# Conn_PWR.net
KiCad netlist of a schematic drawn in Altium Designer
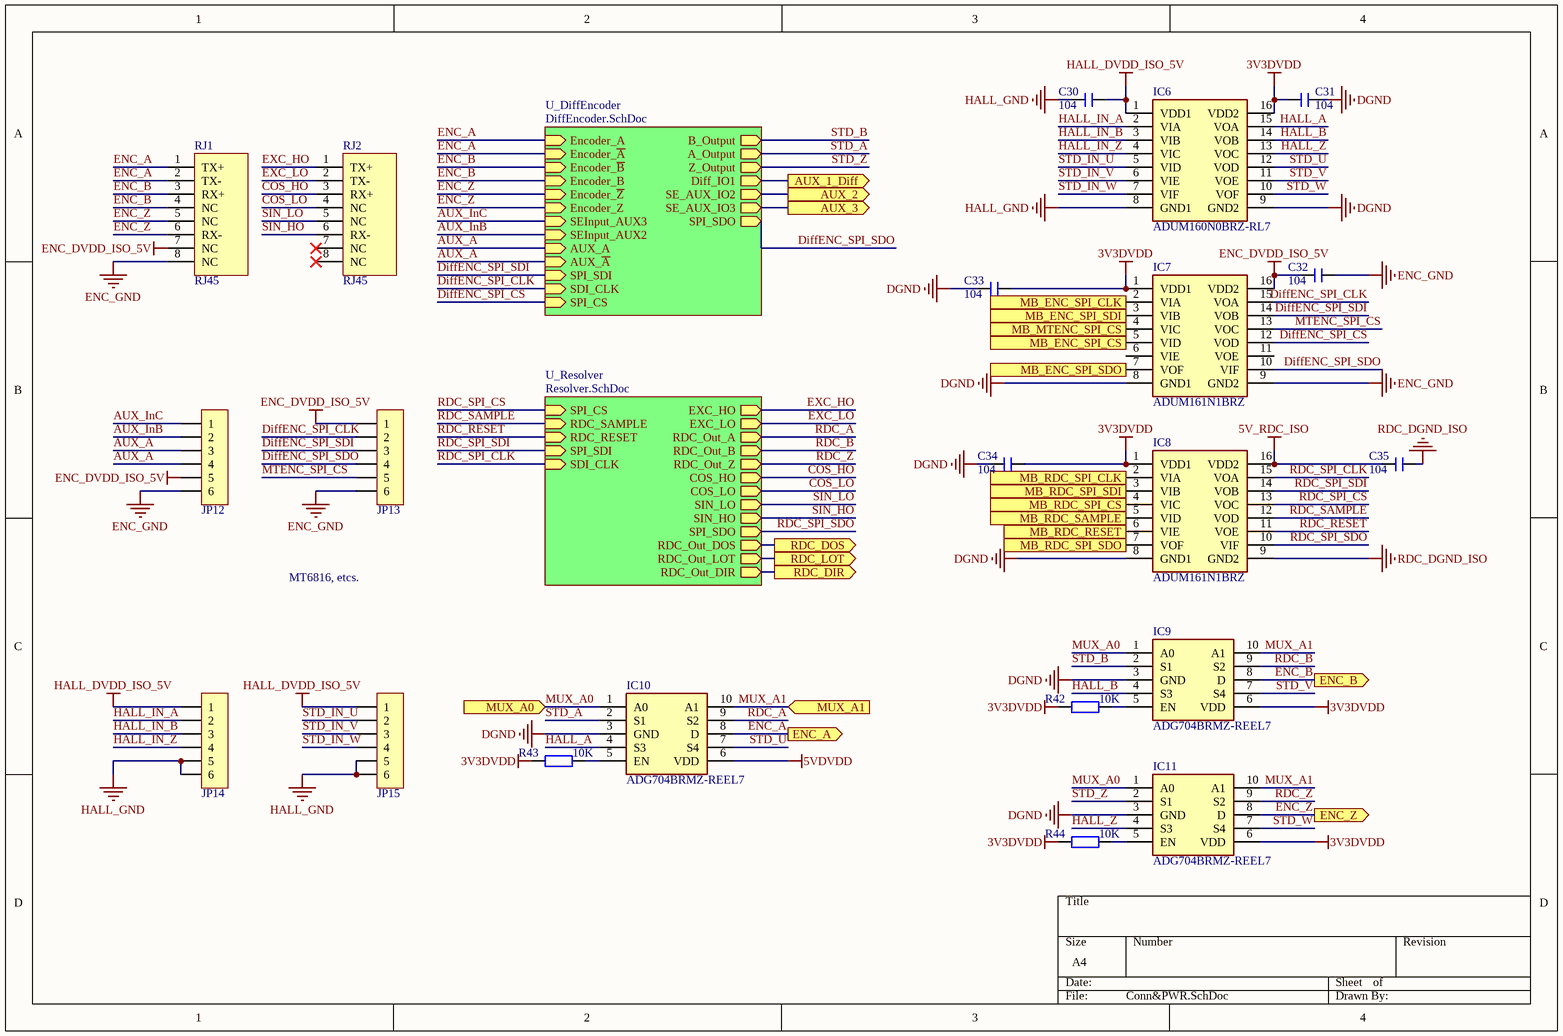
[diagram p0: Conn&PWR.SchDoc]

(export (version "E")
  (design (tool "Eeschema 10.0.6"))
  (components
    (comp (ref "C30")
      (value "104")
      (footprint "C 0603_L")
      (description "贴片电容")
      (libsource (lib "0.1 - 电阻-电容-电感") (part "C"))
    )
    (comp (ref "C31")
      (value "104")
      (footprint "C 0603_L")
      (description "贴片电容")
      (libsource (lib "0.1 - 电阻-电容-电感") (part "C"))
    )
    (comp (ref "C32")
      (value "104")
      (footprint "C 0603_L")
      (description "贴片电容")
      (libsource (lib "0.1 - 电阻-电容-电感") (part "C"))
    )
    (comp (ref "C33")
      (value "104")
      (footprint "C 0603_L")
      (description "贴片电容")
      (libsource (lib "0.1 - 电阻-电容-电感") (part "C"))
    )
    (comp (ref "C34")
      (value "104")
      (footprint "C 0603_L")
      (description "贴片电容")
      (libsource (lib "0.1 - 电阻-电容-电感") (part "C"))
    )
    (comp (ref "C35")
      (value "104")
      (footprint "C 0603_L")
      (description "贴片电容")
      (libsource (lib "0.1 - 电阻-电容-电感") (part "C"))
    )
    (comp (ref "IC6")
      (value "ADUM160N0BRZ-RL7")
      (footprint "SkylakeADPcbLib:SOIC127P600X175-16N")
      (description "Integrated Circuit")
      (fields (field (name "MOUSER PART NUMBER") "584-ADUM160N0BRZ-RL7"))
      (libsource (lib "*") (part "ADUM160N0BRZ-RL7"))
    )
    (comp (ref "IC7")
      (value "ADUM161N1BRZ")
      (footprint "SkylakeADPcbLib:SOIC127P600X175-16N")
      (description "Integrated Circuit")
      (fields (field (name "MOUSER PART NUMBER") "584-ADUM161N1BRZ"))
      (libsource (lib "*") (part "ADUM161N1BRZ"))
    )
    (comp (ref "IC8")
      (value "ADUM161N1BRZ")
      (footprint "SkylakeADPcbLib:SOIC127P600X175-16N")
      (description "Integrated Circuit")
      (fields (field (name "MOUSER PART NUMBER") "584-ADUM161N1BRZ"))
      (libsource (lib "*") (part "ADUM161N1BRZ"))
    )
    (comp (ref "IC9")
      (value "ADG704BRMZ-REEL7")
      (footprint "SkylakeADPcbLib:SOP50P490X110-10N")
      (description "Integrated Circuit")
      (fields (field (name "MOUSER PART NUMBER") "584-ADG704BRMZ-R7"))
      (libsource (lib "*") (part "ADG704BRMZ-REEL7"))
    )
    (comp (ref "IC10")
      (value "ADG704BRMZ-REEL7")
      (footprint "SkylakeADPcbLib:SOP50P490X110-10N")
      (description "Integrated Circuit")
      (fields (field (name "MOUSER PART NUMBER") "584-ADG704BRMZ-R7"))
      (libsource (lib "*") (part "ADG704BRMZ-REEL7"))
    )
    (comp (ref "IC11")
      (value "ADG704BRMZ-REEL7")
      (footprint "SkylakeADPcbLib:SOP50P490X110-10N")
      (description "Integrated Circuit")
      (fields (field (name "MOUSER PART NUMBER") "584-ADG704BRMZ-R7"))
      (libsource (lib "*") (part "ADG704BRMZ-REEL7"))
    )
    (comp (ref "JP12")
      (value "HDR-1X6")
      (footprint "KF2EDGK5.08-LI-6P")
      (description "6P接插件")
      (fields (field (name "版权归属") "封装库来自淘宝卖家 ID：黄晶宝石"))
      (libsource (lib "5.8 - 接插件-脚距5.08 (200mil) ") (part "Header 6"))
    )
    (comp (ref "JP13")
      (value "HDR-1X6")
      (footprint "KF2EDGK5.08-LI-6P")
      (description "6P接插件")
      (fields (field (name "版权归属") "封装库来自淘宝卖家 ID：黄晶宝石"))
      (libsource (lib "5.8 - 接插件-脚距5.08 (200mil) ") (part "Header 6"))
    )
    (comp (ref "JP14")
      (value "HDR-1X6")
      (footprint "KF2EDGK5.08-LI-6P")
      (description "6P接插件")
      (fields (field (name "版权归属") "封装库来自淘宝卖家 ID：黄晶宝石"))
      (libsource (lib "5.8 - 接插件-脚距5.08 (200mil) ") (part "Header 6"))
    )
    (comp (ref "JP15")
      (value "HDR-1X6")
      (footprint "KF2EDGK5.08-LI-6P")
      (description "6P接插件")
      (fields (field (name "版权归属") "封装库来自淘宝卖家 ID：黄晶宝石"))
      (libsource (lib "5.8 - 接插件-脚距5.08 (200mil) ") (part "Header 6"))
    )
    (comp (ref "R42")
      (value "10K")
      (footprint "R 0603_L")
      (description "贴片电阻")
      (fields (field (name "版权归属") "来自淘宝 ID：黄晶宝石"))
      (libsource (lib "0.1 - 电阻-电容-电感") (part "R"))
    )
    (comp (ref "R43")
      (value "10K")
      (footprint "R 0603_L")
      (description "贴片电阻")
      (fields (field (name "版权归属") "来自淘宝 ID：黄晶宝石"))
      (libsource (lib "0.1 - 电阻-电容-电感") (part "R"))
    )
    (comp (ref "R44")
      (value "10K")
      (footprint "R 0603_L")
      (description "贴片电阻")
      (fields (field (name "版权归属") "来自淘宝 ID：黄晶宝石"))
      (libsource (lib "0.1 - 电阻-电容-电感") (part "R"))
    )
    (comp (ref "RJ1")
      (value "RJ45")
      (footprint "RJ45-2")
      (description "以太网接口")
      (libsource (lib "0.8 - 网口-音频插座") (part "RJ45"))
    )
    (comp (ref "RJ2")
      (value "RJ45")
      (footprint "RJ45-2")
      (description "以太网接口")
      (libsource (lib "0.8 - 网口-音频插座") (part "RJ45"))
    )
  )
  (nets
    (net (code "4") (name "/AUX_A") (class "Default")
      (node (ref "JP12") (pin "3") (pinfunction "3_3") (pintype "passive"))
    )
    (net (code "5") (name "/AUX_InB") (class "Default")
      (node (ref "JP12") (pin "2") (pinfunction "2_2") (pintype "passive"))
    )
    (net (code "6") (name "/AUX_InC") (class "Default")
      (node (ref "JP12") (pin "1") (pinfunction "1_1") (pintype "passive"))
    )
    (net (code "7") (name "/AUX_~{A}") (class "Default")
      (node (ref "JP12") (pin "4") (pinfunction "4_4") (pintype "passive"))
    )
    (net (code "8") (name "/COS_HO") (class "Default")
      (node (ref "RJ2") (pin "3") (pinfunction "RX+_3") (pintype "passive"))
    )
    (net (code "9") (name "/COS_LO") (class "Default")
      (node (ref "RJ2") (pin "4") (pinfunction "NC_4") (pintype "passive"))
    )
    (net (code "10") (name "/DiffENC_SPI_CLK") (class "Default")
      (node (ref "IC7") (pin "15") (pinfunction "VOA_15") (pintype "passive"))
      (node (ref "JP13") (pin "2") (pinfunction "2_2") (pintype "passive"))
    )
    (net (code "11") (name "/DiffENC_SPI_CS") (class "Default")
      (node (ref "IC7") (pin "12") (pinfunction "VOD_12") (pintype "passive"))
    )
    (net (code "12") (name "/DiffENC_SPI_SDI") (class "Default")
      (node (ref "IC7") (pin "14") (pinfunction "VOB_14") (pintype "passive"))
      (node (ref "JP13") (pin "3") (pinfunction "3_3") (pintype "passive"))
    )
    (net (code "13") (name "/DiffENC_SPI_SDO") (class "Default")
      (node (ref "IC7") (pin "10") (pinfunction "VIF_10") (pintype "passive"))
      (node (ref "JP13") (pin "4") (pinfunction "4_4") (pintype "passive"))
    )
    (net (code "14") (name "/ENC_A") (class "Default")
      (node (ref "IC10") (pin "8") (pinfunction "D_8") (pintype "passive"))
      (node (ref "RJ1") (pin "1") (pinfunction "TX+_1") (pintype "passive"))
    )
    (net (code "15") (name "/ENC_B") (class "Default")
      (node (ref "IC9") (pin "8") (pinfunction "D_8") (pintype "passive"))
      (node (ref "RJ1") (pin "3") (pinfunction "RX+_3") (pintype "passive"))
    )
    (net (code "16") (name "/ENC_Z") (class "Default")
      (node (ref "IC11") (pin "8") (pinfunction "D_8") (pintype "passive"))
      (node (ref "RJ1") (pin "5") (pinfunction "NC_5") (pintype "passive"))
    )
    (net (code "17") (name "/ENC_~{A}") (class "Default")
      (node (ref "RJ1") (pin "2") (pinfunction "TX-_2") (pintype "passive"))
    )
    (net (code "18") (name "/ENC_~{B}") (class "Default")
      (node (ref "RJ1") (pin "4") (pinfunction "NC_4") (pintype "passive"))
    )
    (net (code "19") (name "/ENC_~{Z}") (class "Default")
      (node (ref "RJ1") (pin "6") (pinfunction "RX-_6") (pintype "passive"))
    )
    (net (code "20") (name "/EXC_HO") (class "Default")
      (node (ref "RJ2") (pin "1") (pinfunction "TX+_1") (pintype "passive"))
    )
    (net (code "21") (name "/EXC_LO") (class "Default")
      (node (ref "RJ2") (pin "2") (pinfunction "TX-_2") (pintype "passive"))
    )
    (net (code "22") (name "/HALL_A") (class "Default")
      (node (ref "IC10") (pin "4") (pinfunction "S3_4") (pintype "passive"))
      (node (ref "IC6") (pin "15") (pinfunction "VOA_15") (pintype "passive"))
    )
    (net (code "23") (name "/HALL_B") (class "Default")
      (node (ref "IC6") (pin "14") (pinfunction "VOB_14") (pintype "passive"))
      (node (ref "IC9") (pin "4") (pinfunction "S3_4") (pintype "passive"))
    )
    (net (code "24") (name "/HALL_IN_A") (class "Default")
      (node (ref "IC6") (pin "2") (pinfunction "VIA_2") (pintype "passive"))
      (node (ref "JP14") (pin "2") (pinfunction "2_2") (pintype "passive"))
    )
    (net (code "25") (name "/HALL_IN_B") (class "Default")
      (node (ref "IC6") (pin "3") (pinfunction "VIB_3") (pintype "passive"))
      (node (ref "JP14") (pin "3") (pinfunction "3_3") (pintype "passive"))
    )
    (net (code "26") (name "/HALL_IN_Z") (class "Default")
      (node (ref "IC6") (pin "4") (pinfunction "VIC_4") (pintype "passive"))
      (node (ref "JP14") (pin "4") (pinfunction "4_4") (pintype "passive"))
    )
    (net (code "27") (name "/HALL_Z") (class "Default")
      (node (ref "IC11") (pin "4") (pinfunction "S3_4") (pintype "passive"))
      (node (ref "IC6") (pin "13") (pinfunction "VOC_13") (pintype "passive"))
    )
    (net (code "28") (name "/MB_ENC_SPI_CLK") (class "Default")
      (node (ref "IC7") (pin "2") (pinfunction "VIA_2") (pintype "passive"))
    )
    (net (code "29") (name "/MB_ENC_SPI_CS") (class "Default")
      (node (ref "IC7") (pin "5") (pinfunction "VID_5") (pintype "passive"))
    )
    (net (code "30") (name "/MB_ENC_SPI_SDI") (class "Default")
      (node (ref "IC7") (pin "3") (pinfunction "VIB_3") (pintype "passive"))
    )
    (net (code "31") (name "/MB_ENC_SPI_SDO") (class "Default")
      (node (ref "IC7") (pin "7") (pinfunction "VOF_7") (pintype "passive"))
    )
    (net (code "32") (name "/MB_MTENC_SPI_CS") (class "Default")
      (node (ref "IC7") (pin "4") (pinfunction "VIC_4") (pintype "passive"))
    )
    (net (code "33") (name "/MB_RDC_RESET") (class "Default")
      (node (ref "IC8") (pin "6") (pinfunction "VIE_6") (pintype "passive"))
    )
    (net (code "34") (name "/MB_RDC_SAMPLE") (class "Default")
      (node (ref "IC8") (pin "5") (pinfunction "VID_5") (pintype "passive"))
    )
    (net (code "35") (name "/MB_RDC_SPI_CLK") (class "Default")
      (node (ref "IC8") (pin "2") (pinfunction "VIA_2") (pintype "passive"))
    )
    (net (code "36") (name "/MB_RDC_SPI_CS") (class "Default")
      (node (ref "IC8") (pin "4") (pinfunction "VIC_4") (pintype "passive"))
    )
    (net (code "37") (name "/MB_RDC_SPI_SDI") (class "Default")
      (node (ref "IC8") (pin "3") (pinfunction "VIB_3") (pintype "passive"))
    )
    (net (code "38") (name "/MB_RDC_SPI_SDO") (class "Default")
      (node (ref "IC8") (pin "7") (pinfunction "VOF_7") (pintype "passive"))
    )
    (net (code "39") (name "/MTENC_SPI_CS") (class "Default")
      (node (ref "IC7") (pin "13") (pinfunction "VOC_13") (pintype "passive"))
      (node (ref "JP13") (pin "5") (pinfunction "5_5") (pintype "passive"))
    )
    (net (code "40") (name "/MUX_A0") (class "Default")
      (node (ref "IC10") (pin "1") (pinfunction "A0_1") (pintype "passive"))
      (node (ref "IC11") (pin "1") (pinfunction "A0_1") (pintype "passive"))
      (node (ref "IC9") (pin "1") (pinfunction "A0_1") (pintype "passive"))
    )
    (net (code "41") (name "/MUX_A1") (class "Default")
      (node (ref "IC10") (pin "10") (pinfunction "A1_10") (pintype "passive"))
      (node (ref "IC11") (pin "10") (pinfunction "A1_10") (pintype "passive"))
      (node (ref "IC9") (pin "10") (pinfunction "A1_10") (pintype "passive"))
    )
    (net (code "42") (name "/RDC_A") (class "Default")
      (node (ref "IC10") (pin "9") (pinfunction "S2_9") (pintype "passive"))
    )
    (net (code "43") (name "/RDC_B") (class "Default")
      (node (ref "IC9") (pin "9") (pinfunction "S2_9") (pintype "passive"))
    )
    (net (code "47") (name "/RDC_RESET") (class "Default")
      (node (ref "IC8") (pin "11") (pinfunction "VOE_11") (pintype "passive"))
    )
    (net (code "48") (name "/RDC_SAMPLE") (class "Default")
      (node (ref "IC8") (pin "12") (pinfunction "VOD_12") (pintype "passive"))
    )
    (net (code "49") (name "/RDC_SPI_CLK") (class "Default")
      (node (ref "IC8") (pin "15") (pinfunction "VOA_15") (pintype "passive"))
    )
    (net (code "50") (name "/RDC_SPI_CS") (class "Default")
      (node (ref "IC8") (pin "13") (pinfunction "VOC_13") (pintype "passive"))
    )
    (net (code "51") (name "/RDC_SPI_SDI") (class "Default")
      (node (ref "IC8") (pin "14") (pinfunction "VOB_14") (pintype "passive"))
    )
    (net (code "52") (name "/RDC_SPI_SDO") (class "Default")
      (node (ref "IC8") (pin "10") (pinfunction "VIF_10") (pintype "passive"))
    )
    (net (code "53") (name "/RDC_Z") (class "Default")
      (node (ref "IC11") (pin "9") (pinfunction "S2_9") (pintype "passive"))
    )
    (net (code "54") (name "/SIN_HO") (class "Default")
      (node (ref "RJ2") (pin "6") (pinfunction "RX-_6") (pintype "passive"))
    )
    (net (code "55") (name "/SIN_LO") (class "Default")
      (node (ref "RJ2") (pin "5") (pinfunction "NC_5") (pintype "passive"))
    )
    (net (code "56") (name "/STD_A") (class "Default")
      (node (ref "IC10") (pin "2") (pinfunction "S1_2") (pintype "passive"))
    )
    (net (code "57") (name "/STD_B") (class "Default")
      (node (ref "IC9") (pin "2") (pinfunction "S1_2") (pintype "passive"))
    )
    (net (code "58") (name "/STD_IN_U") (class "Default")
      (node (ref "IC6") (pin "5") (pinfunction "VID_5") (pintype "passive"))
      (node (ref "JP15") (pin "2") (pinfunction "2_2") (pintype "passive"))
    )
    (net (code "59") (name "/STD_IN_V") (class "Default")
      (node (ref "IC6") (pin "6") (pinfunction "VIE_6") (pintype "passive"))
      (node (ref "JP15") (pin "3") (pinfunction "3_3") (pintype "passive"))
    )
    (net (code "60") (name "/STD_IN_W") (class "Default")
      (node (ref "IC6") (pin "7") (pinfunction "VIF_7") (pintype "passive"))
      (node (ref "JP15") (pin "4") (pinfunction "4_4") (pintype "passive"))
    )
    (net (code "61") (name "/STD_U") (class "Default")
      (node (ref "IC10") (pin "7") (pinfunction "S4_7") (pintype "passive"))
      (node (ref "IC6") (pin "12") (pinfunction "VOD_12") (pintype "passive"))
    )
    (net (code "62") (name "/STD_V") (class "Default")
      (node (ref "IC6") (pin "11") (pinfunction "VOE_11") (pintype "passive"))
      (node (ref "IC9") (pin "7") (pinfunction "S4_7") (pintype "passive"))
    )
    (net (code "63") (name "/STD_W") (class "Default")
      (node (ref "IC11") (pin "7") (pinfunction "S4_7") (pintype "passive"))
      (node (ref "IC6") (pin "10") (pinfunction "VOF_10") (pintype "passive"))
    )
    (net (code "64") (name "/STD_Z") (class "Default")
      (node (ref "IC11") (pin "2") (pinfunction "S1_2") (pintype "passive"))
    )
    (net (code "65") (name "3V3DVDD") (class "Default")
      (node (ref "C31") (pin "2") (pinfunction "2_2") (pintype "passive"))
      (node (ref "C33") (pin "1") (pinfunction "1_1") (pintype "passive"))
      (node (ref "C34") (pin "1") (pinfunction "1_1") (pintype "passive"))
      (node (ref "IC11") (pin "6") (pinfunction "VDD_6") (pintype "passive"))
      (node (ref "IC6") (pin "16") (pinfunction "VDD2_16") (pintype "passive"))
      (node (ref "IC7") (pin "1") (pinfunction "VDD1_1") (pintype "passive"))
      (node (ref "IC8") (pin "1") (pinfunction "VDD1_1") (pintype "passive"))
      (node (ref "IC9") (pin "6") (pinfunction "VDD_6") (pintype "passive"))
      (node (ref "R42") (pin "2") (pinfunction "2_2") (pintype "passive"))
      (node (ref "R43") (pin "2") (pinfunction "2_2") (pintype "passive"))
      (node (ref "R44") (pin "2") (pinfunction "2_2") (pintype "passive"))
    )
    (net (code "66") (name "5VDVDD") (class "Default")
      (node (ref "IC10") (pin "6") (pinfunction "VDD_6") (pintype "passive"))
    )
    (net (code "67") (name "5V_RDC_ISO") (class "Default")
      (node (ref "C35") (pin "2") (pinfunction "2_2") (pintype "passive"))
      (node (ref "IC8") (pin "16") (pinfunction "VDD2_16") (pintype "passive"))
    )
    (net (code "68") (name "DGND") (class "Default")
      (node (ref "C31") (pin "1") (pinfunction "1_1") (pintype "passive"))
      (node (ref "C33") (pin "2") (pinfunction "2_2") (pintype "passive"))
      (node (ref "C34") (pin "2") (pinfunction "2_2") (pintype "passive"))
      (node (ref "IC10") (pin "3") (pinfunction "GND_3") (pintype "passive"))
      (node (ref "IC11") (pin "3") (pinfunction "GND_3") (pintype "passive"))
      (node (ref "IC6") (pin "9") (pinfunction "GND2_9") (pintype "passive"))
      (node (ref "IC7") (pin "8") (pinfunction "GND1_8") (pintype "passive"))
      (node (ref "IC8") (pin "8") (pinfunction "GND1_8") (pintype "passive"))
      (node (ref "IC9") (pin "3") (pinfunction "GND_3") (pintype "passive"))
    )
    (net (code "69") (name "ENC_DVDD_ISO_5V") (class "Default")
      (node (ref "C32") (pin "2") (pinfunction "2_2") (pintype "passive"))
      (node (ref "IC7") (pin "16") (pinfunction "VDD2_16") (pintype "passive"))
      (node (ref "JP12") (pin "5") (pinfunction "5_5") (pintype "passive"))
      (node (ref "JP13") (pin "1") (pinfunction "1_1") (pintype "passive"))
      (node (ref "RJ1") (pin "7") (pinfunction "NC_7") (pintype "passive"))
    )
    (net (code "70") (name "ENC_GND") (class "Default")
      (node (ref "C32") (pin "1") (pinfunction "1_1") (pintype "passive"))
      (node (ref "IC7") (pin "9") (pinfunction "GND2_9") (pintype "passive"))
      (node (ref "JP12") (pin "6") (pinfunction "6_6") (pintype "passive"))
      (node (ref "JP13") (pin "6") (pinfunction "6_6") (pintype "passive"))
      (node (ref "RJ1") (pin "8") (pinfunction "NC_8") (pintype "passive"))
    )
    (net (code "71") (name "HALL_DVDD_ISO_5V") (class "Default")
      (node (ref "C30") (pin "1") (pinfunction "1_1") (pintype "passive"))
      (node (ref "IC6") (pin "1") (pinfunction "VDD1_1") (pintype "passive"))
      (node (ref "JP14") (pin "1") (pinfunction "1_1") (pintype "passive"))
      (node (ref "JP15") (pin "1") (pinfunction "1_1") (pintype "passive"))
    )
    (net (code "72") (name "HALL_GND") (class "Default")
      (node (ref "C30") (pin "2") (pinfunction "2_2") (pintype "passive"))
      (node (ref "IC6") (pin "8") (pinfunction "GND1_8") (pintype "passive"))
      (node (ref "JP14") (pin "5") (pinfunction "5_5") (pintype "passive"))
      (node (ref "JP14") (pin "6") (pinfunction "6_6") (pintype "passive"))
      (node (ref "JP15") (pin "5") (pinfunction "5_5") (pintype "passive"))
      (node (ref "JP15") (pin "6") (pinfunction "6_6") (pintype "passive"))
    )
    (net (code "73") (name "Net-(IC9-EN)") (class "Default")
      (node (ref "IC9") (pin "5") (pinfunction "EN_5") (pintype "passive"))
      (node (ref "R42") (pin "1") (pinfunction "1_1") (pintype "passive"))
    )
    (net (code "74") (name "Net-(IC10-EN)") (class "Default")
      (node (ref "IC10") (pin "5") (pinfunction "EN_5") (pintype "passive"))
      (node (ref "R43") (pin "1") (pinfunction "1_1") (pintype "passive"))
    )
    (net (code "75") (name "Net-(IC11-EN)") (class "Default")
      (node (ref "IC11") (pin "5") (pinfunction "EN_5") (pintype "passive"))
      (node (ref "R44") (pin "1") (pinfunction "1_1") (pintype "passive"))
    )
    (net (code "76") (name "RDC_DGND_ISO") (class "Default")
      (node (ref "C35") (pin "1") (pinfunction "1_1") (pintype "passive"))
      (node (ref "IC8") (pin "9") (pinfunction "GND2_9") (pintype "passive"))
    )
    (net (code "77") (name "unconnected-(IC7-VIE-Pad6)") (class "Default")
      (node (ref "IC7") (pin "6") (pinfunction "VIE_6") (pintype "passive"))
    )
    (net (code "78") (name "unconnected-(IC7-VOE-Pad11)") (class "Default")
      (node (ref "IC7") (pin "11") (pinfunction "VOE_11") (pintype "passive"))
    )
    (net (code "79") (name "unconnected-(RJ2-NC-Pad7)") (class "Default")
      (node (ref "RJ2") (pin "7") (pinfunction "NC_7") (pintype "passive+no_connect"))
    )
    (net (code "80") (name "unconnected-(RJ2-NC-Pad8)") (class "Default")
      (node (ref "RJ2") (pin "8") (pinfunction "NC_8") (pintype "passive+no_connect"))
    )
  )
)
